# 1_MCU.net
KiCad netlist of a schematic drawn in Altium Designer
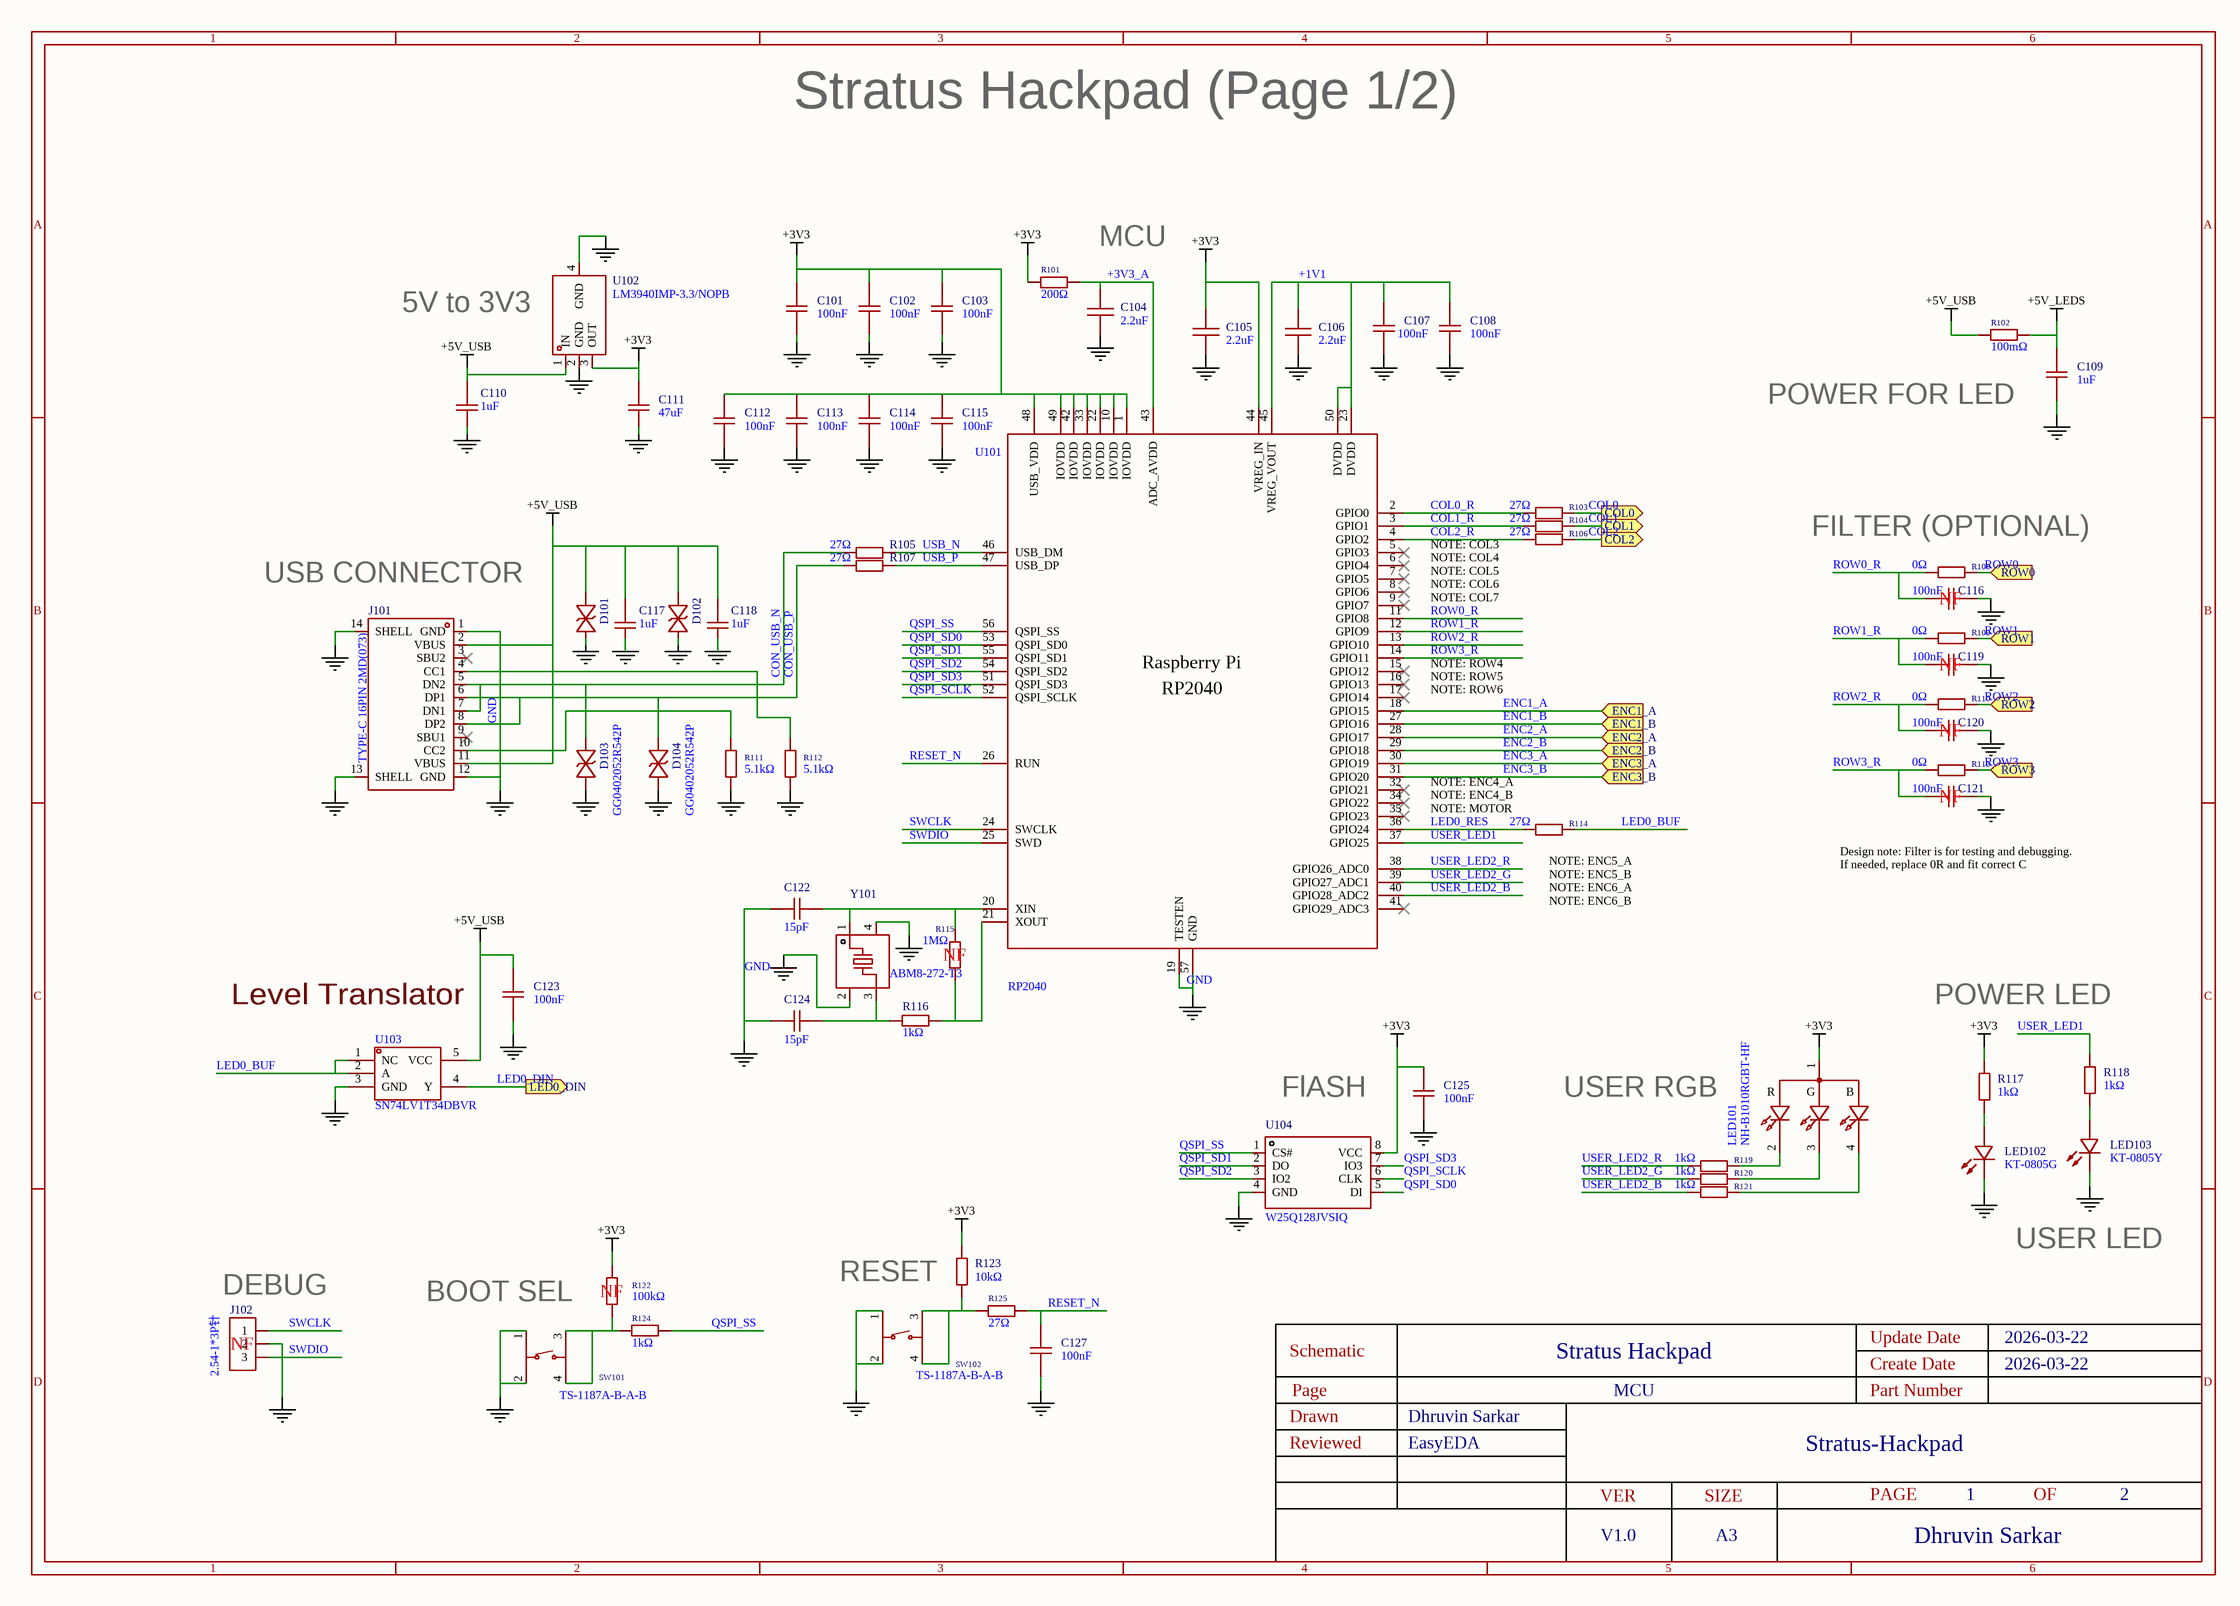
[diagram p0: 1_MCU.schdoc]

(export (version "E")
  (design (tool "Eeschema 10.0.6"))
  (components
    (comp (ref "C101")
      (value "100nF")
      (footprint "C0402")
      (fields
        (field (name "MANUFACTURER") "SAMSUNG(三星)")
        (field (name "MANUFACTURER PART") "CL05B104KO5NNNC")
        (field (name "TOLERANCE") "±10%")
      )
      (libsource (lib "altium-import") (part "root_1_CL05B104KO5NNNC_"))
    )
    (comp (ref "C102")
      (value "100nF")
      (footprint "C0402")
      (fields
        (field (name "MANUFACTURER") "SAMSUNG(三星)")
        (field (name "MANUFACTURER PART") "CL05B104KO5NNNC")
        (field (name "TOLERANCE") "±10%")
      )
      (libsource (lib "altium-import") (part "root_1_CL05B104KO5NNNC_"))
    )
    (comp (ref "C103")
      (value "100nF")
      (footprint "C0402")
      (fields
        (field (name "MANUFACTURER") "SAMSUNG(三星)")
        (field (name "MANUFACTURER PART") "CL05B104KO5NNNC")
        (field (name "TOLERANCE") "±10%")
      )
      (libsource (lib "altium-import") (part "root_1_CL05B104KO5NNNC_"))
    )
    (comp (ref "C104")
      (value "2.2uF")
      (footprint "C0402")
      (fields
        (field (name "MANUFACTURER") "SAMSUNG(三星)")
        (field (name "MANUFACTURER PART") "CL05A225MQ5NSNC")
        (field (name "TOLERANCE") "±20%")
      )
      (libsource (lib "altium-import") (part "root_1_CL05A225MQ5NSNC_"))
    )
    (comp (ref "C105")
      (value "2.2uF")
      (footprint "C0402")
      (fields
        (field (name "MANUFACTURER") "SAMSUNG(三星)")
        (field (name "MANUFACTURER PART") "CL05A225MQ5NSNC")
        (field (name "TOLERANCE") "±20%")
      )
      (libsource (lib "altium-import") (part "root_1_CL05A225MQ5NSNC_"))
    )
    (comp (ref "C106")
      (value "2.2uF")
      (footprint "C0402")
      (fields
        (field (name "MANUFACTURER") "SAMSUNG(三星)")
        (field (name "MANUFACTURER PART") "CL05A225MQ5NSNC")
        (field (name "TOLERANCE") "±20%")
      )
      (libsource (lib "altium-import") (part "root_1_CL05A225MQ5NSNC_"))
    )
    (comp (ref "C107")
      (value "100nF")
      (footprint "C0402")
      (fields
        (field (name "MANUFACTURER") "SAMSUNG(三星)")
        (field (name "MANUFACTURER PART") "CL05B104KO5NNNC")
        (field (name "TOLERANCE") "±10%")
      )
      (libsource (lib "altium-import") (part "root_1_CL05B104KO5NNNC_"))
    )
    (comp (ref "C108")
      (value "100nF")
      (footprint "C0402")
      (fields
        (field (name "MANUFACTURER") "SAMSUNG(三星)")
        (field (name "MANUFACTURER PART") "CL05B104KO5NNNC")
        (field (name "TOLERANCE") "±10%")
      )
      (libsource (lib "altium-import") (part "root_1_CL05B104KO5NNNC_"))
    )
    (comp (ref "C109")
      (value "1uF")
      (footprint "C0402")
      (fields
        (field (name "MANUFACTURER") "SAMSUNG(三星)")
        (field (name "MANUFACTURER PART") "CL05A105KA5NQNC")
        (field (name "TOLERANCE") "±10%")
      )
      (libsource (lib "altium-import") (part "root_1_CL05A105KA5NQNC_"))
    )
    (comp (ref "C110")
      (value "1uF")
      (footprint "C0402")
      (fields
        (field (name "MANUFACTURER") "SAMSUNG(三星)")
        (field (name "MANUFACTURER PART") "CL05A105KA5NQNC")
        (field (name "TOLERANCE") "±10%")
      )
      (libsource (lib "altium-import") (part "root_1_CL05A105KA5NQNC_"))
    )
    (comp (ref "C111")
      (value "47uF")
      (footprint "C1206")
      (fields
        (field (name "MANUFACTURER") "SAMSUNG(三星)")
        (field (name "MANUFACTURER PART") "CL31A476MPHNNNE")
        (field (name "TOLERANCE") "±20%")
      )
      (libsource (lib "altium-import") (part "root_1_CL31A476MPHNNNE_"))
    )
    (comp (ref "C112")
      (value "100nF")
      (footprint "C0402")
      (fields
        (field (name "MANUFACTURER") "SAMSUNG(三星)")
        (field (name "MANUFACTURER PART") "CL05B104KO5NNNC")
        (field (name "TOLERANCE") "±10%")
      )
      (libsource (lib "altium-import") (part "root_1_CL05B104KO5NNNC_"))
    )
    (comp (ref "C113")
      (value "100nF")
      (footprint "C0402")
      (fields
        (field (name "MANUFACTURER") "SAMSUNG(三星)")
        (field (name "MANUFACTURER PART") "CL05B104KO5NNNC")
        (field (name "TOLERANCE") "±10%")
      )
      (libsource (lib "altium-import") (part "root_1_CL05B104KO5NNNC_"))
    )
    (comp (ref "C114")
      (value "100nF")
      (footprint "C0402")
      (fields
        (field (name "MANUFACTURER") "SAMSUNG(三星)")
        (field (name "MANUFACTURER PART") "CL05B104KO5NNNC")
        (field (name "TOLERANCE") "±10%")
      )
      (libsource (lib "altium-import") (part "root_1_CL05B104KO5NNNC_"))
    )
    (comp (ref "C115")
      (value "100nF")
      (footprint "C0402")
      (fields
        (field (name "MANUFACTURER") "SAMSUNG(三星)")
        (field (name "MANUFACTURER PART") "CL05B104KO5NNNC")
        (field (name "TOLERANCE") "±10%")
      )
      (libsource (lib "altium-import") (part "root_1_CL05B104KO5NNNC_"))
    )
    (comp (ref "C116")
      (value "100nF")
      (footprint "C0402")
      (fields
        (field (name "MANUFACTURER") "SAMSUNG(三星)")
        (field (name "MANUFACTURER PART") "CL05B104KO5NNNC")
        (field (name "TOLERANCE") "±10%")
      )
      (libsource (lib "altium-import") (part "root_2_CL05B104KO5NNNC_"))
    )
    (comp (ref "C117")
      (value "1uF")
      (footprint "C0402")
      (fields
        (field (name "MANUFACTURER") "SAMSUNG(三星)")
        (field (name "MANUFACTURER PART") "CL05A105KA5NQNC")
        (field (name "TOLERANCE") "±10%")
      )
      (libsource (lib "altium-import") (part "root_1_CL05A105KA5NQNC_"))
    )
    (comp (ref "C118")
      (value "1uF")
      (footprint "C0402")
      (fields
        (field (name "MANUFACTURER") "SAMSUNG(三星)")
        (field (name "MANUFACTURER PART") "CL05A105KA5NQNC")
        (field (name "TOLERANCE") "±10%")
      )
      (libsource (lib "altium-import") (part "root_1_CL05A105KA5NQNC_"))
    )
    (comp (ref "C119")
      (value "100nF")
      (footprint "C0402")
      (fields
        (field (name "MANUFACTURER") "SAMSUNG(三星)")
        (field (name "MANUFACTURER PART") "CL05B104KO5NNNC")
        (field (name "TOLERANCE") "±10%")
      )
      (libsource (lib "altium-import") (part "root_2_CL05B104KO5NNNC_"))
    )
    (comp (ref "C120")
      (value "100nF")
      (footprint "C0402")
      (fields
        (field (name "MANUFACTURER") "SAMSUNG(三星)")
        (field (name "MANUFACTURER PART") "CL05B104KO5NNNC")
        (field (name "TOLERANCE") "±10%")
      )
      (libsource (lib "altium-import") (part "root_2_CL05B104KO5NNNC_"))
    )
    (comp (ref "C121")
      (value "100nF")
      (footprint "C0402")
      (fields
        (field (name "MANUFACTURER") "SAMSUNG(三星)")
        (field (name "MANUFACTURER PART") "CL05B104KO5NNNC")
        (field (name "TOLERANCE") "±10%")
      )
      (libsource (lib "altium-import") (part "root_2_CL05B104KO5NNNC_"))
    )
    (comp (ref "C122")
      (value "15pF")
      (footprint "C0402")
      (fields
        (field (name "MANUFACTURER") "SAMSUNG(三星)")
        (field (name "MANUFACTURER PART") "CL05C150JB5NNNC")
        (field (name "TOLERANCE") "±5%")
      )
      (libsource (lib "altium-import") (part "root_1_CL05C150JB5NNNC_"))
    )
    (comp (ref "C123")
      (value "100nF")
      (footprint "C0402")
      (fields
        (field (name "MANUFACTURER") "SAMSUNG(三星)")
        (field (name "MANUFACTURER PART") "CL05B104KO5NNNC")
        (field (name "TOLERANCE") "±10%")
      )
      (libsource (lib "altium-import") (part "root_1_CL05B104KO5NNNC_"))
    )
    (comp (ref "C124")
      (value "15pF")
      (footprint "C0402")
      (fields
        (field (name "MANUFACTURER") "SAMSUNG(三星)")
        (field (name "MANUFACTURER PART") "CL05C150JB5NNNC")
        (field (name "TOLERANCE") "±5%")
      )
      (libsource (lib "altium-import") (part "root_1_CL05C150JB5NNNC_"))
    )
    (comp (ref "C125")
      (value "100nF")
      (footprint "C0402")
      (fields
        (field (name "MANUFACTURER") "SAMSUNG(三星)")
        (field (name "MANUFACTURER PART") "CL05B104KO5NNNC")
        (field (name "TOLERANCE") "±10%")
      )
      (libsource (lib "altium-import") (part "root_1_CL05B104KO5NNNC_"))
    )
    (comp (ref "C127")
      (value "100nF")
      (footprint "C0402")
      (fields
        (field (name "MANUFACTURER") "SAMSUNG(三星)")
        (field (name "MANUFACTURER PART") "CL05B104KO5NNNC")
        (field (name "TOLERANCE") "±10%")
      )
      (libsource (lib "altium-import") (part "root_1_CL05B104KO5NNNC_"))
    )
    (comp (ref "D101")
      (value "GG0402052R542P")
      (footprint "D0402-BI")
      (fields (field (name "MANUFACTURER") "Kyocera AVX"))
      (libsource (lib "altium-import") (part "root_1_GG0402052R542P_"))
    )
    (comp (ref "D102")
      (value "GG0402052R542P")
      (footprint "D0402-BI")
      (fields (field (name "MANUFACTURER") "Kyocera AVX"))
      (libsource (lib "altium-import") (part "root_1_GG0402052R542P_"))
    )
    (comp (ref "D103")
      (value "GG0402052R542P")
      (footprint "D0402-BI")
      (fields (field (name "MANUFACTURER") "Kyocera AVX"))
      (libsource (lib "altium-import") (part "root_1_GG0402052R542P_"))
    )
    (comp (ref "D104")
      (value "GG0402052R542P")
      (footprint "D0402-BI")
      (fields (field (name "MANUFACTURER") "Kyocera AVX"))
      (libsource (lib "altium-import") (part "root_1_GG0402052R542P_"))
    )
    (comp (ref "J101")
      (value "TYPE-C 16PIN 2MD(073)")
      (footprint "USB-C-SMD_TYPE-C-6PIN-2MD-073")
      (fields (field (name "MANUFACTURER") "SHOU HAN(首韩)"))
      (libsource (lib "altium-import") (part "root_0_mirrored_TYPE-C 16PIN 2MD(073)_"))
    )
    (comp (ref "J102")
      (value "2.54-1*3P针")
      (footprint "HDR-TH_3P-P2.54-V-M-1")
      (fields (field (name "MANUFACTURER") "BOOMELE(博穆精密)"))
      (libsource (lib "altium-import") (part "root_0_mirrored_2.54-1*3P针_"))
    )
    (comp (ref "LED101")
      (value "NH-B1010RGBT-HF")
      (footprint "LED-ARRAY-SMD_4P-L1.0-W1.0-TR_NH-B1010RGBT_1")
      (fields (field (name "MANUFACTURER") "国星光电"))
      (libsource (lib "altium-import") (part "root_0_NH-B1010RGBT-HF_RF_v1.0_"))
    )
    (comp (ref "LED102")
      (value "KT-0805G")
      (footprint "LED0805-R-RD")
      (fields (field (name "MANUFACTURER") "KENTO"))
      (libsource (lib "altium-import") (part "root_1_KT-0805G_"))
    )
    (comp (ref "LED103")
      (value "KT-0805Y")
      (footprint "LED0805-R-RD")
      (fields (field (name "MANUFACTURER") "KENTO"))
      (libsource (lib "altium-import") (part "root_1_KT-0805Y_"))
    )
    (comp (ref "R101")
      (value "200Ω")
      (footprint "R0402")
      (fields
        (field (name "MANUFACTURER") "UNI-ROYAL(厚声)")
        (field (name "MANUFACTURER PART") "0402WGF2000TCE")
        (field (name "TOLERANCE") "±1%")
      )
      (libsource (lib "altium-import") (part "root_0_0402WGF2000TCE_"))
    )
    (comp (ref "R102")
      (value "100mΩ")
      (footprint "R1206")
      (fields
        (field (name "MANUFACTURER") "UNI-ROYAL(厚声)")
        (field (name "MANUFACTURER PART") "1206W4F100LT5E")
        (field (name "TOLERANCE") "±1%")
      )
      (libsource (lib "altium-import") (part "root_0_1206W4F100LT5E_"))
    )
    (comp (ref "R103")
      (value "27Ω")
      (footprint "R0402")
      (fields
        (field (name "MANUFACTURER") "UNI-ROYAL(厚声)")
        (field (name "MANUFACTURER PART") "0402WGF270JTCE")
        (field (name "TOLERANCE") "±1%")
      )
      (libsource (lib "altium-import") (part "root_0_0402WGF270JTCE_"))
    )
    (comp (ref "R104")
      (value "27Ω")
      (footprint "R0402")
      (fields
        (field (name "MANUFACTURER") "UNI-ROYAL(厚声)")
        (field (name "MANUFACTURER PART") "0402WGF270JTCE")
        (field (name "TOLERANCE") "±1%")
      )
      (libsource (lib "altium-import") (part "root_0_0402WGF270JTCE_"))
    )
    (comp (ref "R105")
      (value "27Ω")
      (footprint "R0402")
      (fields
        (field (name "MANUFACTURER") "UNI-ROYAL(厚声)")
        (field (name "MANUFACTURER PART") "0402WGF270JTCE")
        (field (name "TOLERANCE") "±1%")
      )
      (libsource (lib "altium-import") (part "root_0_0402WGF270JTCE_"))
    )
    (comp (ref "R106")
      (value "27Ω")
      (footprint "R0402")
      (fields
        (field (name "MANUFACTURER") "UNI-ROYAL(厚声)")
        (field (name "MANUFACTURER PART") "0402WGF270JTCE")
        (field (name "TOLERANCE") "±1%")
      )
      (libsource (lib "altium-import") (part "root_0_0402WGF270JTCE_"))
    )
    (comp (ref "R107")
      (value "27Ω")
      (footprint "R0402")
      (fields
        (field (name "MANUFACTURER") "UNI-ROYAL(厚声)")
        (field (name "MANUFACTURER PART") "0402WGF270JTCE")
        (field (name "TOLERANCE") "±1%")
      )
      (libsource (lib "altium-import") (part "root_0_0402WGF270JTCE_"))
    )
    (comp (ref "R108")
      (value "0Ω")
      (footprint "R0402")
      (fields
        (field (name "MANUFACTURER") "UNI-ROYAL(厚声)")
        (field (name "MANUFACTURER PART") "0402WGF0000TCE")
        (field (name "TOLERANCE") "±1%")
      )
      (libsource (lib "altium-import") (part "root_0_0402WGF0000TCE_"))
    )
    (comp (ref "R109")
      (value "0Ω")
      (footprint "R0402")
      (fields
        (field (name "MANUFACTURER") "UNI-ROYAL(厚声)")
        (field (name "MANUFACTURER PART") "0402WGF0000TCE")
        (field (name "TOLERANCE") "±1%")
      )
      (libsource (lib "altium-import") (part "root_0_0402WGF0000TCE_"))
    )
    (comp (ref "R110")
      (value "0Ω")
      (footprint "R0402")
      (fields
        (field (name "MANUFACTURER") "UNI-ROYAL(厚声)")
        (field (name "MANUFACTURER PART") "0402WGF0000TCE")
        (field (name "TOLERANCE") "±1%")
      )
      (libsource (lib "altium-import") (part "root_0_0402WGF0000TCE_"))
    )
    (comp (ref "R111")
      (value "5.1kΩ")
      (footprint "R0402")
      (fields
        (field (name "MANUFACTURER") "UNI-ROYAL(厚声)")
        (field (name "MANUFACTURER PART") "0402WGF5101TCE")
        (field (name "TOLERANCE") "±1%")
      )
      (libsource (lib "altium-import") (part "root_1_0402WGF5101TCE_"))
    )
    (comp (ref "R112")
      (value "5.1kΩ")
      (footprint "R0402")
      (fields
        (field (name "MANUFACTURER") "UNI-ROYAL(厚声)")
        (field (name "MANUFACTURER PART") "0402WGF5101TCE")
        (field (name "TOLERANCE") "±1%")
      )
      (libsource (lib "altium-import") (part "root_1_0402WGF5101TCE_"))
    )
    (comp (ref "R113")
      (value "0Ω")
      (footprint "R0402")
      (fields
        (field (name "MANUFACTURER") "UNI-ROYAL(厚声)")
        (field (name "MANUFACTURER PART") "0402WGF0000TCE")
        (field (name "TOLERANCE") "±1%")
      )
      (libsource (lib "altium-import") (part "root_0_0402WGF0000TCE_"))
    )
    (comp (ref "R114")
      (value "27Ω")
      (footprint "R0402")
      (fields
        (field (name "MANUFACTURER") "UNI-ROYAL(厚声)")
        (field (name "MANUFACTURER PART") "0402WGF270JTCE")
        (field (name "TOLERANCE") "±1%")
      )
      (libsource (lib "altium-import") (part "root_0_0402WGF270JTCE_"))
    )
    (comp (ref "R115")
      (value "1MΩ")
      (footprint "R0402")
      (fields
        (field (name "MANUFACTURER") "UNI-ROYAL(厚声)")
        (field (name "MANUFACTURER PART") "0402WGF1004TCE")
        (field (name "TOLERANCE") "±1%")
      )
      (libsource (lib "altium-import") (part "root_1_0402WGF1004TCE_"))
    )
    (comp (ref "R116")
      (value "1kΩ")
      (footprint "R0402")
      (fields
        (field (name "MANUFACTURER") "UNI-ROYAL(厚声)")
        (field (name "MANUFACTURER PART") "0402WGF1001TCE")
        (field (name "TOLERANCE") "±1%")
      )
      (libsource (lib "altium-import") (part "root_0_0402WGF1001TCE_"))
    )
    (comp (ref "R117")
      (value "1kΩ")
      (footprint "R0402")
      (fields
        (field (name "MANUFACTURER") "UNI-ROYAL(厚声)")
        (field (name "MANUFACTURER PART") "0402WGF1001TCE")
        (field (name "TOLERANCE") "±1%")
      )
      (libsource (lib "altium-import") (part "root_1_0402WGF1001TCE_"))
    )
    (comp (ref "R118")
      (value "1kΩ")
      (footprint "R0402")
      (fields
        (field (name "MANUFACTURER") "UNI-ROYAL(厚声)")
        (field (name "MANUFACTURER PART") "0402WGF1001TCE")
        (field (name "TOLERANCE") "±1%")
      )
      (libsource (lib "altium-import") (part "root_1_0402WGF1001TCE_"))
    )
    (comp (ref "R119")
      (value "1kΩ")
      (footprint "R0402")
      (fields
        (field (name "MANUFACTURER") "UNI-ROYAL(厚声)")
        (field (name "MANUFACTURER PART") "0402WGF1001TCE")
        (field (name "TOLERANCE") "±1%")
      )
      (libsource (lib "altium-import") (part "root_2_0402WGF1001TCE_"))
    )
    (comp (ref "R120")
      (value "1kΩ")
      (footprint "R0402")
      (fields
        (field (name "MANUFACTURER") "UNI-ROYAL(厚声)")
        (field (name "MANUFACTURER PART") "0402WGF1001TCE")
        (field (name "TOLERANCE") "±1%")
      )
      (libsource (lib "altium-import") (part "root_2_0402WGF1001TCE_"))
    )
    (comp (ref "R121")
      (value "1kΩ")
      (footprint "R0402")
      (fields
        (field (name "MANUFACTURER") "UNI-ROYAL(厚声)")
        (field (name "MANUFACTURER PART") "0402WGF1001TCE")
        (field (name "TOLERANCE") "±1%")
      )
      (libsource (lib "altium-import") (part "root_2_0402WGF1001TCE_"))
    )
    (comp (ref "R122")
      (value "100kΩ")
      (footprint "R0402")
      (fields
        (field (name "MANUFACTURER") "UNI-ROYAL(厚声)")
        (field (name "MANUFACTURER PART") "0402WGF1003TCE")
        (field (name "TOLERANCE") "±1%")
      )
      (libsource (lib "altium-import") (part "root_1_0402WGF1003TCE_"))
    )
    (comp (ref "R123")
      (value "10kΩ")
      (footprint "R0402")
      (fields
        (field (name "MANUFACTURER") "UNI-ROYAL(厚声)")
        (field (name "MANUFACTURER PART") "0402WGF1002TCE")
        (field (name "TOLERANCE") "±1%")
      )
      (libsource (lib "altium-import") (part "root_1_0402WGF1002TCE_"))
    )
    (comp (ref "R124")
      (value "1kΩ")
      (footprint "R0402")
      (fields
        (field (name "MANUFACTURER") "UNI-ROYAL(厚声)")
        (field (name "MANUFACTURER PART") "0402WGF1001TCE")
        (field (name "TOLERANCE") "±1%")
      )
      (libsource (lib "altium-import") (part "root_0_0402WGF1001TCE_"))
    )
    (comp (ref "R125")
      (value "27Ω")
      (footprint "R0402")
      (fields
        (field (name "MANUFACTURER") "UNI-ROYAL(厚声)")
        (field (name "MANUFACTURER PART") "0402WGF270JTCE")
        (field (name "TOLERANCE") "±1%")
      )
      (libsource (lib "altium-import") (part "root_0_0402WGF270JTCE_"))
    )
    (comp (ref "SW101")
      (value "TS-1187A-B-A-B")
      (footprint "SW-SMD_4P-L5.1-W5.1-P3.70-LS6.5-TL-2")
      (fields (field (name "MANUFACTURER") "XKB Connectivity(中国星坤)"))
      (libsource (lib "altium-import") (part "root_3_mirrored_TS-1187A-B-A-B_"))
    )
    (comp (ref "SW102")
      (value "TS-1187A-B-A-B")
      (footprint "SW-SMD_4P-L5.1-W5.1-P3.70-LS6.5-TL-2")
      (fields (field (name "MANUFACTURER") "XKB Connectivity(中国星坤)"))
      (libsource (lib "altium-import") (part "root_3_mirrored_TS-1187A-B-A-B_"))
    )
    (comp (ref "U101")
      (value "RP2040")
      (footprint "LQFN-56_L7.0-W7.0-P0.4-EP_1")
      (fields (field (name "MANUFACTURER") "Raspberry Pi(树莓派)"))
      (libsource (lib "altium-import") (part "root_0_RP2040_C2040_DS_v1.0_"))
    )
    (comp (ref "U102")
      (value "LM3940IMP-3.3/NOPB")
      (footprint "SOT-223_L6.5-W3.5-P2.30-LS7.0-BR")
      (fields (field (name "MANUFACTURER") "TI(德州仪器)"))
      (libsource (lib "altium-import") (part "root_1_LM3940IMP-3.3/NOPB_"))
    )
    (comp (ref "U103")
      (value "SN74LV1T34DBVR")
      (footprint "SOT-23-5_L2.9-W1.6-P0.95-LS2.8-BR")
      (fields (field (name "MANUFACTURER") "TI(德州仪器)"))
      (libsource (lib "altium-import") (part "root_0_SN74LV1T34DBVR_RF_v1.0_"))
    )
    (comp (ref "U104")
      (value "W25Q128JVSIQ")
      (footprint "SOIC-8_L5.3-W5.3-P1.27-LS8.0-BL")
      (fields (field (name "MANUFACTURER") "WINBOND(华邦)"))
      (libsource (lib "altium-import") (part "root_0_W25Q128JVSIQ_"))
    )
    (comp (ref "Y101")
      (value "ABM8-272-T3")
      (footprint "CRYSTAL-SMD_4P-L3.2-W2.5-BL")
      (fields (field (name "MANUFACTURER") "ABRACON"))
      (libsource (lib "altium-import") (part "root_3_ABM8-272-T3_C20625731_"))
    )
  )
  (nets
    (net (code "1") (name "+3V3") (class "Default")
      (node (ref "C101") (pin "2") (pinfunction "2_2") (pintype "passive"))
      (node (ref "C102") (pin "2") (pinfunction "2_2") (pintype "passive"))
      (node (ref "C103") (pin "2") (pinfunction "2_2") (pintype "passive"))
      (node (ref "C105") (pin "2") (pinfunction "2_2") (pintype "passive"))
      (node (ref "C111") (pin "2") (pinfunction "2_2") (pintype "passive"))
      (node (ref "C112") (pin "2") (pinfunction "2_2") (pintype "passive"))
      (node (ref "C113") (pin "2") (pinfunction "2_2") (pintype "passive"))
      (node (ref "C114") (pin "2") (pinfunction "2_2") (pintype "passive"))
      (node (ref "C115") (pin "2") (pinfunction "2_2") (pintype "passive"))
      (node (ref "C125") (pin "2") (pinfunction "2_2") (pintype "passive"))
      (node (ref "LED101") (pin "1") (pinfunction "+_1") (pintype "passive"))
      (node (ref "R101") (pin "1") (pinfunction "1_1") (pintype "passive"))
      (node (ref "R117") (pin "2") (pinfunction "2_2") (pintype "passive"))
      (node (ref "R122") (pin "2") (pinfunction "2_2") (pintype "passive"))
      (node (ref "R123") (pin "2") (pinfunction "2_2") (pintype "passive"))
      (node (ref "U101") (pin "1") (pinfunction "IOVDD_1") (pintype "passive"))
      (node (ref "U101") (pin "10") (pinfunction "IOVDD_10") (pintype "passive"))
      (node (ref "U101") (pin "22") (pinfunction "IOVDD_22") (pintype "passive"))
      (node (ref "U101") (pin "33") (pinfunction "IOVDD_33") (pintype "passive"))
      (node (ref "U101") (pin "42") (pinfunction "IOVDD_42") (pintype "passive"))
      (node (ref "U101") (pin "44") (pinfunction "VREG_IN_44") (pintype "passive"))
      (node (ref "U101") (pin "48") (pinfunction "USB_VDD_48") (pintype "passive"))
      (node (ref "U101") (pin "49") (pinfunction "IOVDD_49") (pintype "passive"))
      (node (ref "U102") (pin "3") (pinfunction "OUT_3") (pintype "passive"))
      (node (ref "U104") (pin "8") (pinfunction "VCC_8") (pintype "passive"))
    )
    (net (code "2") (name "+5V_LEDS") (class "Default")
      (node (ref "C109") (pin "2") (pinfunction "2_2") (pintype "passive"))
      (node (ref "R102") (pin "2") (pinfunction "2_2") (pintype "passive"))
    )
    (net (code "3") (name "+5V_USB") (class "Default")
      (node (ref "C110") (pin "2") (pinfunction "2_2") (pintype "passive"))
      (node (ref "C117") (pin "2") (pinfunction "2_2") (pintype "passive"))
      (node (ref "C118") (pin "2") (pinfunction "2_2") (pintype "passive"))
      (node (ref "C123") (pin "2") (pinfunction "2_2") (pintype "passive"))
      (node (ref "D101") (pin "2") (pinfunction "2_2") (pintype "passive"))
      (node (ref "D102") (pin "2") (pinfunction "2_2") (pintype "passive"))
      (node (ref "J101") (pin "11") (pinfunction "VBUS_11") (pintype "passive"))
      (node (ref "J101") (pin "2") (pinfunction "VBUS_2") (pintype "passive"))
      (node (ref "R102") (pin "1") (pinfunction "1_1") (pintype "passive"))
      (node (ref "U102") (pin "1") (pinfunction "IN_1") (pintype "passive"))
      (node (ref "U103") (pin "5") (pinfunction "VCC_5") (pintype "passive"))
    )
    (net (code "4") (name "/+1V1") (class "Default")
      (node (ref "C106") (pin "2") (pinfunction "2_2") (pintype "passive"))
      (node (ref "C107") (pin "2") (pinfunction "2_2") (pintype "passive"))
      (node (ref "C108") (pin "2") (pinfunction "2_2") (pintype "passive"))
      (node (ref "U101") (pin "23") (pinfunction "DVDD_23") (pintype "passive"))
      (node (ref "U101") (pin "45") (pinfunction "VREG_VOUT_45") (pintype "passive"))
      (node (ref "U101") (pin "50") (pinfunction "DVDD_50") (pintype "passive"))
    )
    (net (code "5") (name "/+3V3_A") (class "Default")
      (node (ref "C104") (pin "2") (pinfunction "2_2") (pintype "passive"))
      (node (ref "R101") (pin "2") (pinfunction "2_2") (pintype "passive"))
      (node (ref "U101") (pin "43") (pinfunction "ADC_AVDD_43") (pintype "passive"))
    )
    (net (code "6") (name "/COL0") (class "Default")
      (node (ref "R103") (pin "2") (pinfunction "2_2") (pintype "passive"))
    )
    (net (code "7") (name "/COL0_R") (class "Default")
      (node (ref "R103") (pin "1") (pinfunction "1_1") (pintype "passive"))
      (node (ref "U101") (pin "2") (pinfunction "GPIO0_2") (pintype "passive"))
    )
    (net (code "8") (name "/COL1") (class "Default")
      (node (ref "R104") (pin "2") (pinfunction "2_2") (pintype "passive"))
    )
    (net (code "9") (name "/COL1_R") (class "Default")
      (node (ref "R104") (pin "1") (pinfunction "1_1") (pintype "passive"))
      (node (ref "U101") (pin "3") (pinfunction "GPIO1_3") (pintype "passive"))
    )
    (net (code "10") (name "/COL2") (class "Default")
      (node (ref "R106") (pin "2") (pinfunction "2_2") (pintype "passive"))
    )
    (net (code "11") (name "/COL2_R") (class "Default")
      (node (ref "R106") (pin "1") (pinfunction "1_1") (pintype "passive"))
      (node (ref "U101") (pin "4") (pinfunction "GPIO2_4") (pintype "passive"))
    )
    (net (code "12") (name "/CON_USB_N") (class "Default")
      (node (ref "D103") (pin "2") (pinfunction "2_2") (pintype "passive"))
      (node (ref "J101") (pin "5") (pinfunction "DN2_5") (pintype "passive"))
      (node (ref "J101") (pin "7") (pinfunction "DN1_7") (pintype "passive"))
      (node (ref "R105") (pin "1") (pinfunction "1_1") (pintype "passive"))
    )
    (net (code "13") (name "/ENC1_A") (class "Default")
      (node (ref "U101") (pin "18") (pinfunction "GPIO15_18") (pintype "passive"))
    )
    (net (code "14") (name "/ENC1_B") (class "Default")
      (node (ref "U101") (pin "27") (pinfunction "GPIO16_27") (pintype "passive"))
    )
    (net (code "15") (name "/ENC2_A") (class "Default")
      (node (ref "U101") (pin "28") (pinfunction "GPIO17_28") (pintype "passive"))
    )
    (net (code "16") (name "/ENC2_B") (class "Default")
      (node (ref "U101") (pin "29") (pinfunction "GPIO18_29") (pintype "passive"))
    )
    (net (code "17") (name "/ENC3_A") (class "Default")
      (node (ref "U101") (pin "30") (pinfunction "GPIO19_30") (pintype "passive"))
    )
    (net (code "18") (name "/ENC3_B") (class "Default")
      (node (ref "U101") (pin "31") (pinfunction "GPIO20_31") (pintype "passive"))
    )
    (net (code "19") (name "/LED0_BUF") (class "Default")
      (node (ref "R114") (pin "2") (pinfunction "2_2") (pintype "passive"))
      (node (ref "U103") (pin "1") (pinfunction "NC_1") (pintype "passive"))
      (node (ref "U103") (pin "2") (pinfunction "A_2") (pintype "passive"))
    )
    (net (code "20") (name "/LED0_DIN") (class "Default")
      (node (ref "U103") (pin "4") (pinfunction "Y_4") (pintype "passive"))
    )
    (net (code "21") (name "/LED0_RES") (class "Default")
      (node (ref "R114") (pin "1") (pinfunction "1_1") (pintype "passive"))
      (node (ref "U101") (pin "36") (pinfunction "GPIO24_36") (pintype "passive"))
    )
    (net (code "22") (name "/QSPI_SCLK") (class "Default")
      (node (ref "U101") (pin "52") (pinfunction "QSPI_SCLK_52") (pintype "passive"))
      (node (ref "U104") (pin "6") (pinfunction "CLK_6") (pintype "passive"))
    )
    (net (code "23") (name "/QSPI_SD0") (class "Default")
      (node (ref "U101") (pin "53") (pinfunction "QSPI_SD0_53") (pintype "passive"))
      (node (ref "U104") (pin "5") (pinfunction "DI_5") (pintype "passive"))
    )
    (net (code "24") (name "/QSPI_SD1") (class "Default")
      (node (ref "U101") (pin "55") (pinfunction "QSPI_SD1_55") (pintype "passive"))
      (node (ref "U104") (pin "2") (pinfunction "DO_2") (pintype "passive"))
    )
    (net (code "25") (name "/QSPI_SD2") (class "Default")
      (node (ref "U101") (pin "54") (pinfunction "QSPI_SD2_54") (pintype "passive"))
      (node (ref "U104") (pin "3") (pinfunction "IO2_3") (pintype "passive"))
    )
    (net (code "26") (name "/QSPI_SD3") (class "Default")
      (node (ref "U101") (pin "51") (pinfunction "QSPI_SD3_51") (pintype "passive"))
      (node (ref "U104") (pin "7") (pinfunction "IO3_7") (pintype "passive"))
    )
    (net (code "27") (name "/QSPI_SS") (class "Default")
      (node (ref "R124") (pin "2") (pinfunction "2_2") (pintype "passive"))
      (node (ref "U101") (pin "56") (pinfunction "QSPI_SS_56") (pintype "passive"))
      (node (ref "U104") (pin "1") (pinfunction "CS#_1") (pintype "passive"))
    )
    (net (code "28") (name "/RESET_N") (class "Default")
      (node (ref "C127") (pin "2") (pinfunction "2_2") (pintype "passive"))
      (node (ref "R125") (pin "2") (pinfunction "2_2") (pintype "passive"))
      (node (ref "U101") (pin "26") (pinfunction "RUN_26") (pintype "passive"))
    )
    (net (code "29") (name "/ROW0") (class "Default")
      (node (ref "R108") (pin "2") (pinfunction "2_2") (pintype "passive"))
    )
    (net (code "30") (name "/ROW0_R") (class "Default")
      (node (ref "C116") (pin "2") (pinfunction "2_2") (pintype "passive"))
      (node (ref "R108") (pin "1") (pinfunction "1_1") (pintype "passive"))
      (node (ref "U101") (pin "11") (pinfunction "GPIO8_11") (pintype "passive"))
    )
    (net (code "31") (name "/ROW1") (class "Default")
      (node (ref "R109") (pin "2") (pinfunction "2_2") (pintype "passive"))
    )
    (net (code "32") (name "/ROW1_R") (class "Default")
      (node (ref "C119") (pin "2") (pinfunction "2_2") (pintype "passive"))
      (node (ref "R109") (pin "1") (pinfunction "1_1") (pintype "passive"))
      (node (ref "U101") (pin "12") (pinfunction "GPIO9_12") (pintype "passive"))
    )
    (net (code "33") (name "/ROW2") (class "Default")
      (node (ref "R110") (pin "2") (pinfunction "2_2") (pintype "passive"))
    )
    (net (code "34") (name "/ROW2_R") (class "Default")
      (node (ref "C120") (pin "2") (pinfunction "2_2") (pintype "passive"))
      (node (ref "R110") (pin "1") (pinfunction "1_1") (pintype "passive"))
      (node (ref "U101") (pin "13") (pinfunction "GPIO10_13") (pintype "passive"))
    )
    (net (code "35") (name "/ROW3") (class "Default")
      (node (ref "R113") (pin "2") (pinfunction "2_2") (pintype "passive"))
    )
    (net (code "36") (name "/ROW3_R") (class "Default")
      (node (ref "C121") (pin "2") (pinfunction "2_2") (pintype "passive"))
      (node (ref "R113") (pin "1") (pinfunction "1_1") (pintype "passive"))
      (node (ref "U101") (pin "14") (pinfunction "GPIO11_14") (pintype "passive"))
    )
    (net (code "37") (name "/SWCLK") (class "Default")
      (node (ref "J102") (pin "1") (pinfunction "1_1") (pintype "passive"))
      (node (ref "U101") (pin "24") (pinfunction "SWCLK_24") (pintype "passive"))
    )
    (net (code "38") (name "/SWDIO") (class "Default")
      (node (ref "J102") (pin "3") (pinfunction "3_3") (pintype "passive"))
      (node (ref "U101") (pin "25") (pinfunction "SWD_25") (pintype "passive"))
    )
    (net (code "39") (name "/USB_N") (class "Default")
      (node (ref "R105") (pin "2") (pinfunction "2_2") (pintype "passive"))
      (node (ref "U101") (pin "46") (pinfunction "USB_DM_46") (pintype "passive"))
    )
    (net (code "40") (name "/USB_P") (class "Default")
      (node (ref "R107") (pin "2") (pinfunction "2_2") (pintype "passive"))
      (node (ref "U101") (pin "47") (pinfunction "USB_DP_47") (pintype "passive"))
    )
    (net (code "41") (name "/USER_LED1") (class "Default")
      (node (ref "R118") (pin "2") (pinfunction "2_2") (pintype "passive"))
      (node (ref "U101") (pin "37") (pinfunction "GPIO25_37") (pintype "passive"))
    )
    (net (code "42") (name "/USER_LED2_B") (class "Default")
      (node (ref "R121") (pin "2") (pinfunction "2_2") (pintype "passive"))
      (node (ref "U101") (pin "40") (pinfunction "GPIO28_ADC2_40") (pintype "passive"))
    )
    (net (code "43") (name "/USER_LED2_G") (class "Default")
      (node (ref "R120") (pin "2") (pinfunction "2_2") (pintype "passive"))
      (node (ref "U101") (pin "39") (pinfunction "GPIO27_ADC1_39") (pintype "passive"))
    )
    (net (code "44") (name "/USER_LED2_R") (class "Default")
      (node (ref "R119") (pin "2") (pinfunction "2_2") (pintype "passive"))
      (node (ref "U101") (pin "38") (pinfunction "GPIO26_ADC0_38") (pintype "passive"))
    )
    (net (code "45") (name "GND") (class "Default")
      (node (ref "C101") (pin "1") (pinfunction "1_1") (pintype "passive"))
      (node (ref "C102") (pin "1") (pinfunction "1_1") (pintype "passive"))
      (node (ref "C103") (pin "1") (pinfunction "1_1") (pintype "passive"))
      (node (ref "C104") (pin "1") (pinfunction "1_1") (pintype "passive"))
      (node (ref "C105") (pin "1") (pinfunction "1_1") (pintype "passive"))
      (node (ref "C106") (pin "1") (pinfunction "1_1") (pintype "passive"))
      (node (ref "C107") (pin "1") (pinfunction "1_1") (pintype "passive"))
      (node (ref "C108") (pin "1") (pinfunction "1_1") (pintype "passive"))
      (node (ref "C109") (pin "1") (pinfunction "1_1") (pintype "passive"))
      (node (ref "C110") (pin "1") (pinfunction "1_1") (pintype "passive"))
      (node (ref "C111") (pin "1") (pinfunction "1_1") (pintype "passive"))
      (node (ref "C112") (pin "1") (pinfunction "1_1") (pintype "passive"))
      (node (ref "C113") (pin "1") (pinfunction "1_1") (pintype "passive"))
      (node (ref "C114") (pin "1") (pinfunction "1_1") (pintype "passive"))
      (node (ref "C115") (pin "1") (pinfunction "1_1") (pintype "passive"))
      (node (ref "C116") (pin "1") (pinfunction "1_1") (pintype "passive"))
      (node (ref "C117") (pin "1") (pinfunction "1_1") (pintype "passive"))
      (node (ref "C118") (pin "1") (pinfunction "1_1") (pintype "passive"))
      (node (ref "C119") (pin "1") (pinfunction "1_1") (pintype "passive"))
      (node (ref "C120") (pin "1") (pinfunction "1_1") (pintype "passive"))
      (node (ref "C121") (pin "1") (pinfunction "1_1") (pintype "passive"))
      (node (ref "C122") (pin "2") (pinfunction "2_2") (pintype "passive"))
      (node (ref "C123") (pin "1") (pinfunction "1_1") (pintype "passive"))
      (node (ref "C124") (pin "2") (pinfunction "2_2") (pintype "passive"))
      (node (ref "C125") (pin "1") (pinfunction "1_1") (pintype "passive"))
      (node (ref "C127") (pin "1") (pinfunction "1_1") (pintype "passive"))
      (node (ref "D101") (pin "1") (pinfunction "1_1") (pintype "passive"))
      (node (ref "D102") (pin "1") (pinfunction "1_1") (pintype "passive"))
      (node (ref "D103") (pin "1") (pinfunction "1_1") (pintype "passive"))
      (node (ref "D104") (pin "1") (pinfunction "1_1") (pintype "passive"))
      (node (ref "D104") (pin "2") (pinfunction "2_2") (pintype "passive"))
      (node (ref "J101") (pin "1") (pinfunction "GND_1") (pintype "passive"))
      (node (ref "J101") (pin "12") (pinfunction "GND_12") (pintype "passive"))
      (node (ref "J101") (pin "13") (pinfunction "SHELL_13") (pintype "passive"))
      (node (ref "J101") (pin "14") (pinfunction "SHELL_14") (pintype "passive"))
      (node (ref "J101") (pin "6") (pinfunction "DP1_6") (pintype "passive"))
      (node (ref "J101") (pin "8") (pinfunction "DP2_8") (pintype "passive"))
      (node (ref "J102") (pin "2") (pinfunction "2_2") (pintype "passive"))
      (node (ref "LED102") (pin "2") (pinfunction "K_2") (pintype "passive"))
      (node (ref "LED103") (pin "2") (pinfunction "-_2") (pintype "passive"))
      (node (ref "R107") (pin "1") (pinfunction "1_1") (pintype "passive"))
      (node (ref "R111") (pin "1") (pinfunction "1_1") (pintype "passive"))
      (node (ref "R112") (pin "1") (pinfunction "1_1") (pintype "passive"))
      (node (ref "SW101") (pin "1") (pinfunction "A_1") (pintype "passive"))
      (node (ref "SW101") (pin "2") (pinfunction "B_2") (pintype "passive"))
      (node (ref "SW102") (pin "1") (pinfunction "A_1") (pintype "passive"))
      (node (ref "SW102") (pin "2") (pinfunction "B_2") (pintype "passive"))
      (node (ref "U101") (pin "19") (pinfunction "TESTEN_19") (pintype "passive"))
      (node (ref "U101") (pin "57") (pinfunction "GND_57") (pintype "passive"))
      (node (ref "U102") (pin "2") (pinfunction "GND_2") (pintype "passive"))
      (node (ref "U102") (pin "4") (pinfunction "GND_4") (pintype "passive"))
      (node (ref "U103") (pin "3") (pinfunction "GND_3") (pintype "passive"))
      (node (ref "U104") (pin "4") (pinfunction "GND_4") (pintype "passive"))
      (node (ref "Y101") (pin "2") (pinfunction "GND_2") (pintype "passive"))
      (node (ref "Y101") (pin "4") (pinfunction "GND_4") (pintype "passive"))
    )
    (net (code "46") (name "Net-(C124-Pad1)") (class "Default")
      (node (ref "C124") (pin "1") (pinfunction "1_1") (pintype "passive"))
      (node (ref "R116") (pin "1") (pinfunction "1_1") (pintype "passive"))
      (node (ref "Y101") (pin "3") (pinfunction "3_3") (pintype "passive"))
    )
    (net (code "47") (name "Net-(J101-CC1)") (class "Default")
      (node (ref "J101") (pin "4") (pinfunction "CC1_4") (pintype "passive"))
      (node (ref "R112") (pin "2") (pinfunction "2_2") (pintype "passive"))
    )
    (net (code "48") (name "Net-(J101-CC2)") (class "Default")
      (node (ref "J101") (pin "10") (pinfunction "CC2_10") (pintype "passive"))
      (node (ref "R111") (pin "2") (pinfunction "2_2") (pintype "passive"))
    )
    (net (code "49") (name "Net-(LED101---Pad2)") (class "Default")
      (node (ref "LED101") (pin "2") (pinfunction "-_2") (pintype "passive"))
      (node (ref "R119") (pin "1") (pinfunction "1_1") (pintype "passive"))
    )
    (net (code "50") (name "Net-(LED101---Pad3)") (class "Default")
      (node (ref "LED101") (pin "3") (pinfunction "-_3") (pintype "passive"))
      (node (ref "R120") (pin "1") (pinfunction "1_1") (pintype "passive"))
    )
    (net (code "51") (name "Net-(LED101---Pad4)") (class "Default")
      (node (ref "LED101") (pin "4") (pinfunction "-_4") (pintype "passive"))
      (node (ref "R121") (pin "1") (pinfunction "1_1") (pintype "passive"))
    )
    (net (code "52") (name "Net-(LED102-A)") (class "Default")
      (node (ref "LED102") (pin "1") (pinfunction "A_1") (pintype "passive"))
      (node (ref "R117") (pin "1") (pinfunction "1_1") (pintype "passive"))
    )
    (net (code "53") (name "Net-(LED103-+)") (class "Default")
      (node (ref "LED103") (pin "1") (pinfunction "+_1") (pintype "passive"))
      (node (ref "R118") (pin "1") (pinfunction "1_1") (pintype "passive"))
    )
    (net (code "54") (name "Net-(SW101-C)") (class "Default")
      (node (ref "R122") (pin "1") (pinfunction "1_1") (pintype "passive"))
      (node (ref "R124") (pin "1") (pinfunction "1_1") (pintype "passive"))
      (node (ref "SW101") (pin "3") (pinfunction "C_3") (pintype "passive"))
      (node (ref "SW101") (pin "4") (pinfunction "D_4") (pintype "passive"))
    )
    (net (code "55") (name "Net-(SW102-C)") (class "Default")
      (node (ref "R123") (pin "1") (pinfunction "1_1") (pintype "passive"))
      (node (ref "R125") (pin "1") (pinfunction "1_1") (pintype "passive"))
      (node (ref "SW102") (pin "3") (pinfunction "C_3") (pintype "passive"))
      (node (ref "SW102") (pin "4") (pinfunction "D_4") (pintype "passive"))
    )
    (net (code "56") (name "Net-(U101-XIN)") (class "Default")
      (node (ref "C122") (pin "1") (pinfunction "1_1") (pintype "passive"))
      (node (ref "R115") (pin "2") (pinfunction "2_2") (pintype "passive"))
      (node (ref "U101") (pin "20") (pinfunction "XIN_20") (pintype "passive"))
      (node (ref "Y101") (pin "1") (pinfunction "1_1") (pintype "passive"))
    )
    (net (code "57") (name "Net-(U101-XOUT)") (class "Default")
      (node (ref "R115") (pin "1") (pinfunction "1_1") (pintype "passive"))
      (node (ref "R116") (pin "2") (pinfunction "2_2") (pintype "passive"))
      (node (ref "U101") (pin "21") (pinfunction "XOUT_21") (pintype "passive"))
    )
    (net (code "58") (name "unconnected-(J101-SBU1-Pad9)") (class "Default")
      (node (ref "J101") (pin "9") (pinfunction "SBU1_9") (pintype "passive+no_connect"))
    )
    (net (code "59") (name "unconnected-(J101-SBU2-Pad3)") (class "Default")
      (node (ref "J101") (pin "3") (pinfunction "SBU2_3") (pintype "passive+no_connect"))
    )
    (net (code "60") (name "unconnected-(U101-GPIO3-Pad5)") (class "Default")
      (node (ref "U101") (pin "5") (pinfunction "GPIO3_5") (pintype "passive+no_connect"))
    )
    (net (code "61") (name "unconnected-(U101-GPIO4-Pad6)") (class "Default")
      (node (ref "U101") (pin "6") (pinfunction "GPIO4_6") (pintype "passive+no_connect"))
    )
    (net (code "62") (name "unconnected-(U101-GPIO5-Pad7)") (class "Default")
      (node (ref "U101") (pin "7") (pinfunction "GPIO5_7") (pintype "passive+no_connect"))
    )
    (net (code "63") (name "unconnected-(U101-GPIO6-Pad8)") (class "Default")
      (node (ref "U101") (pin "8") (pinfunction "GPIO6_8") (pintype "passive+no_connect"))
    )
    (net (code "64") (name "unconnected-(U101-GPIO7-Pad9)") (class "Default")
      (node (ref "U101") (pin "9") (pinfunction "GPIO7_9") (pintype "passive+no_connect"))
    )
    (net (code "65") (name "unconnected-(U101-GPIO12-Pad15)") (class "Default")
      (node (ref "U101") (pin "15") (pinfunction "GPIO12_15") (pintype "passive+no_connect"))
    )
    (net (code "66") (name "unconnected-(U101-GPIO13-Pad16)") (class "Default")
      (node (ref "U101") (pin "16") (pinfunction "GPIO13_16") (pintype "passive+no_connect"))
    )
    (net (code "67") (name "unconnected-(U101-GPIO14-Pad17)") (class "Default")
      (node (ref "U101") (pin "17") (pinfunction "GPIO14_17") (pintype "passive+no_connect"))
    )
    (net (code "68") (name "unconnected-(U101-GPIO21-Pad32)") (class "Default")
      (node (ref "U101") (pin "32") (pinfunction "GPIO21_32") (pintype "passive+no_connect"))
    )
    (net (code "69") (name "unconnected-(U101-GPIO22-Pad34)") (class "Default")
      (node (ref "U101") (pin "34") (pinfunction "GPIO22_34") (pintype "passive+no_connect"))
    )
    (net (code "70") (name "unconnected-(U101-GPIO23-Pad35)") (class "Default")
      (node (ref "U101") (pin "35") (pinfunction "GPIO23_35") (pintype "passive+no_connect"))
    )
    (net (code "71") (name "unconnected-(U101-GPIO29_ADC3-Pad41)") (class "Default")
      (node (ref "U101") (pin "41") (pinfunction "GPIO29_ADC3_41") (pintype "passive+no_connect"))
    )
  )
)
